# aprs_tracker_v4.net
KiCad netlist of a schematic drawn in EAGLE
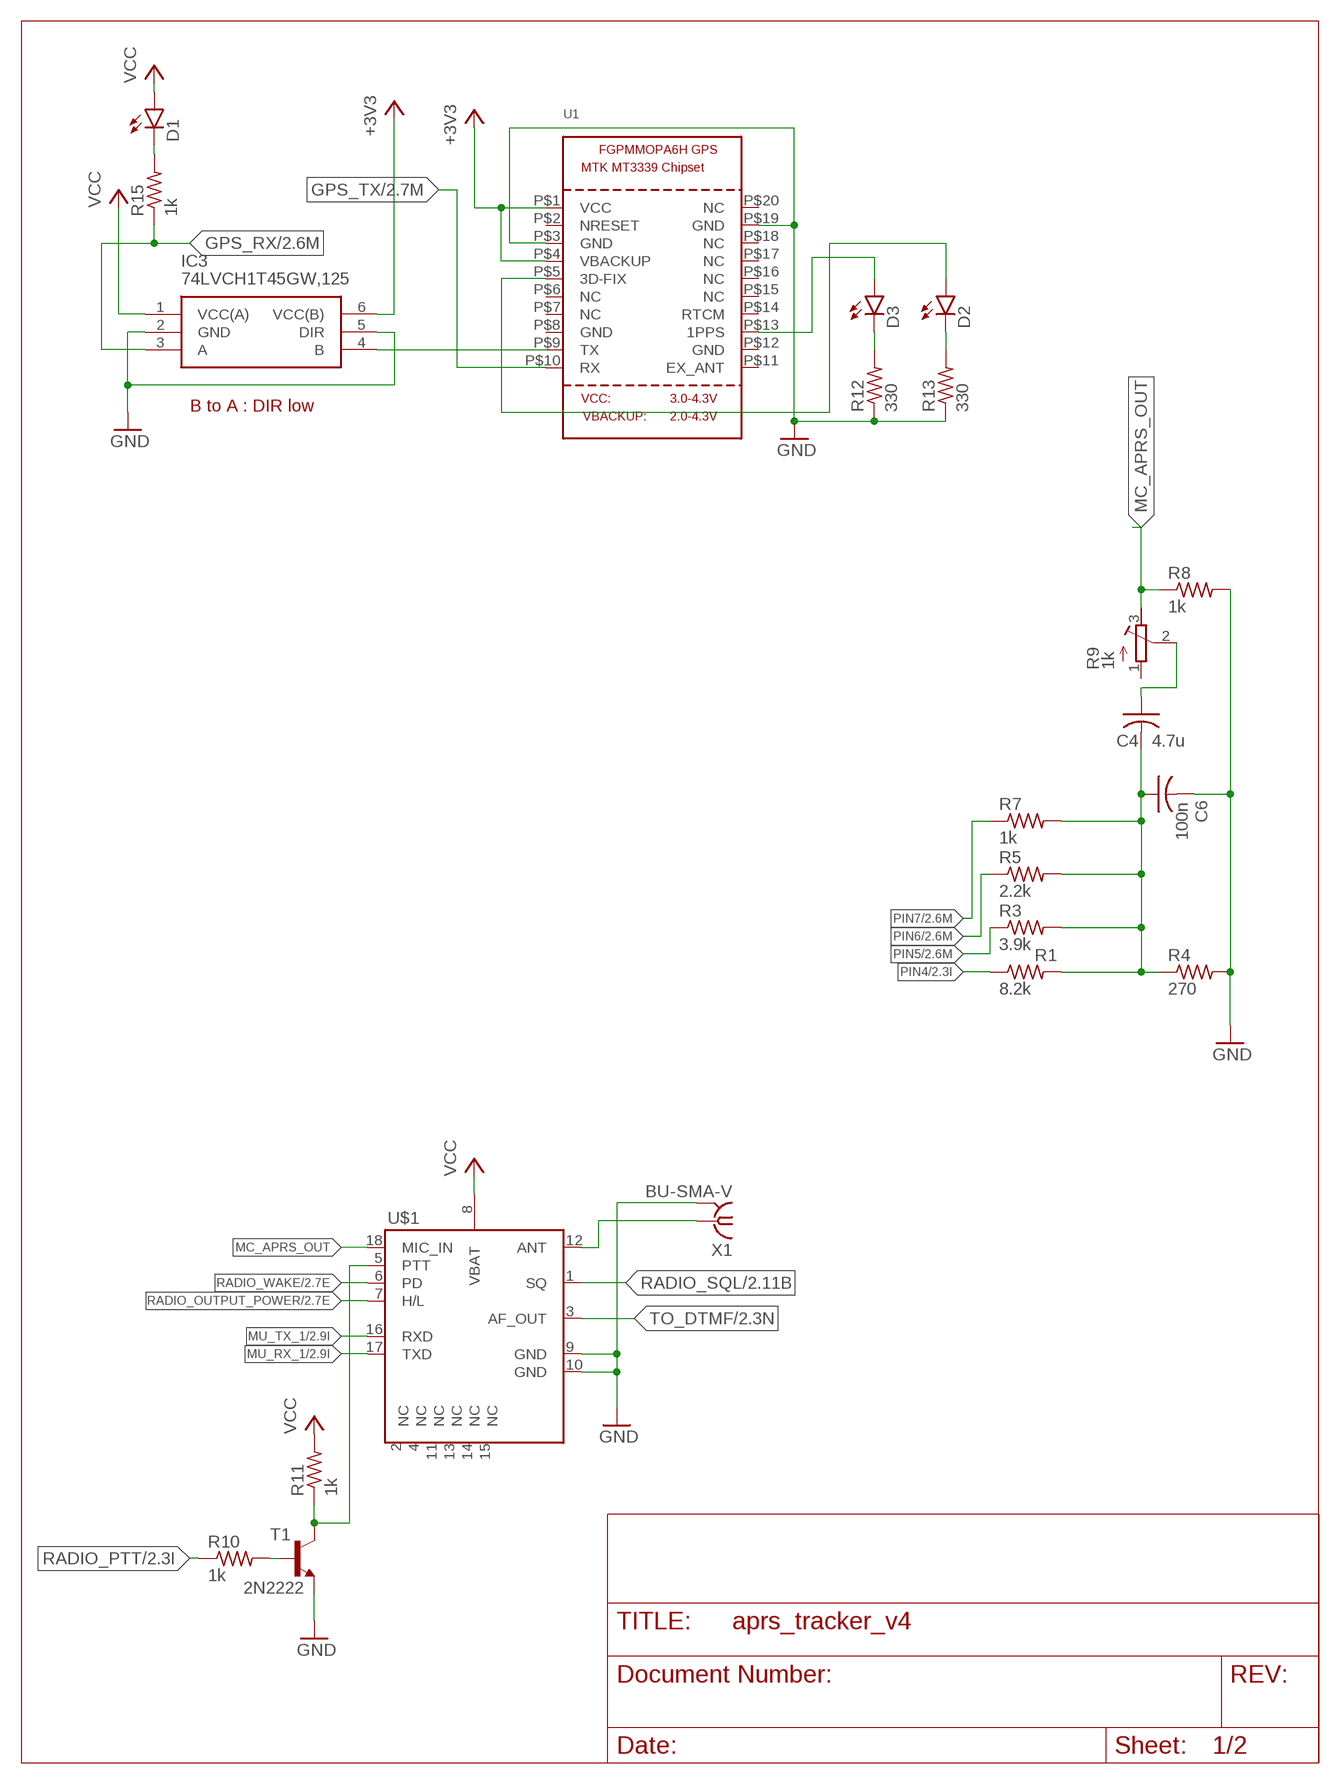
[diagram p0: schematic, sheet 1]
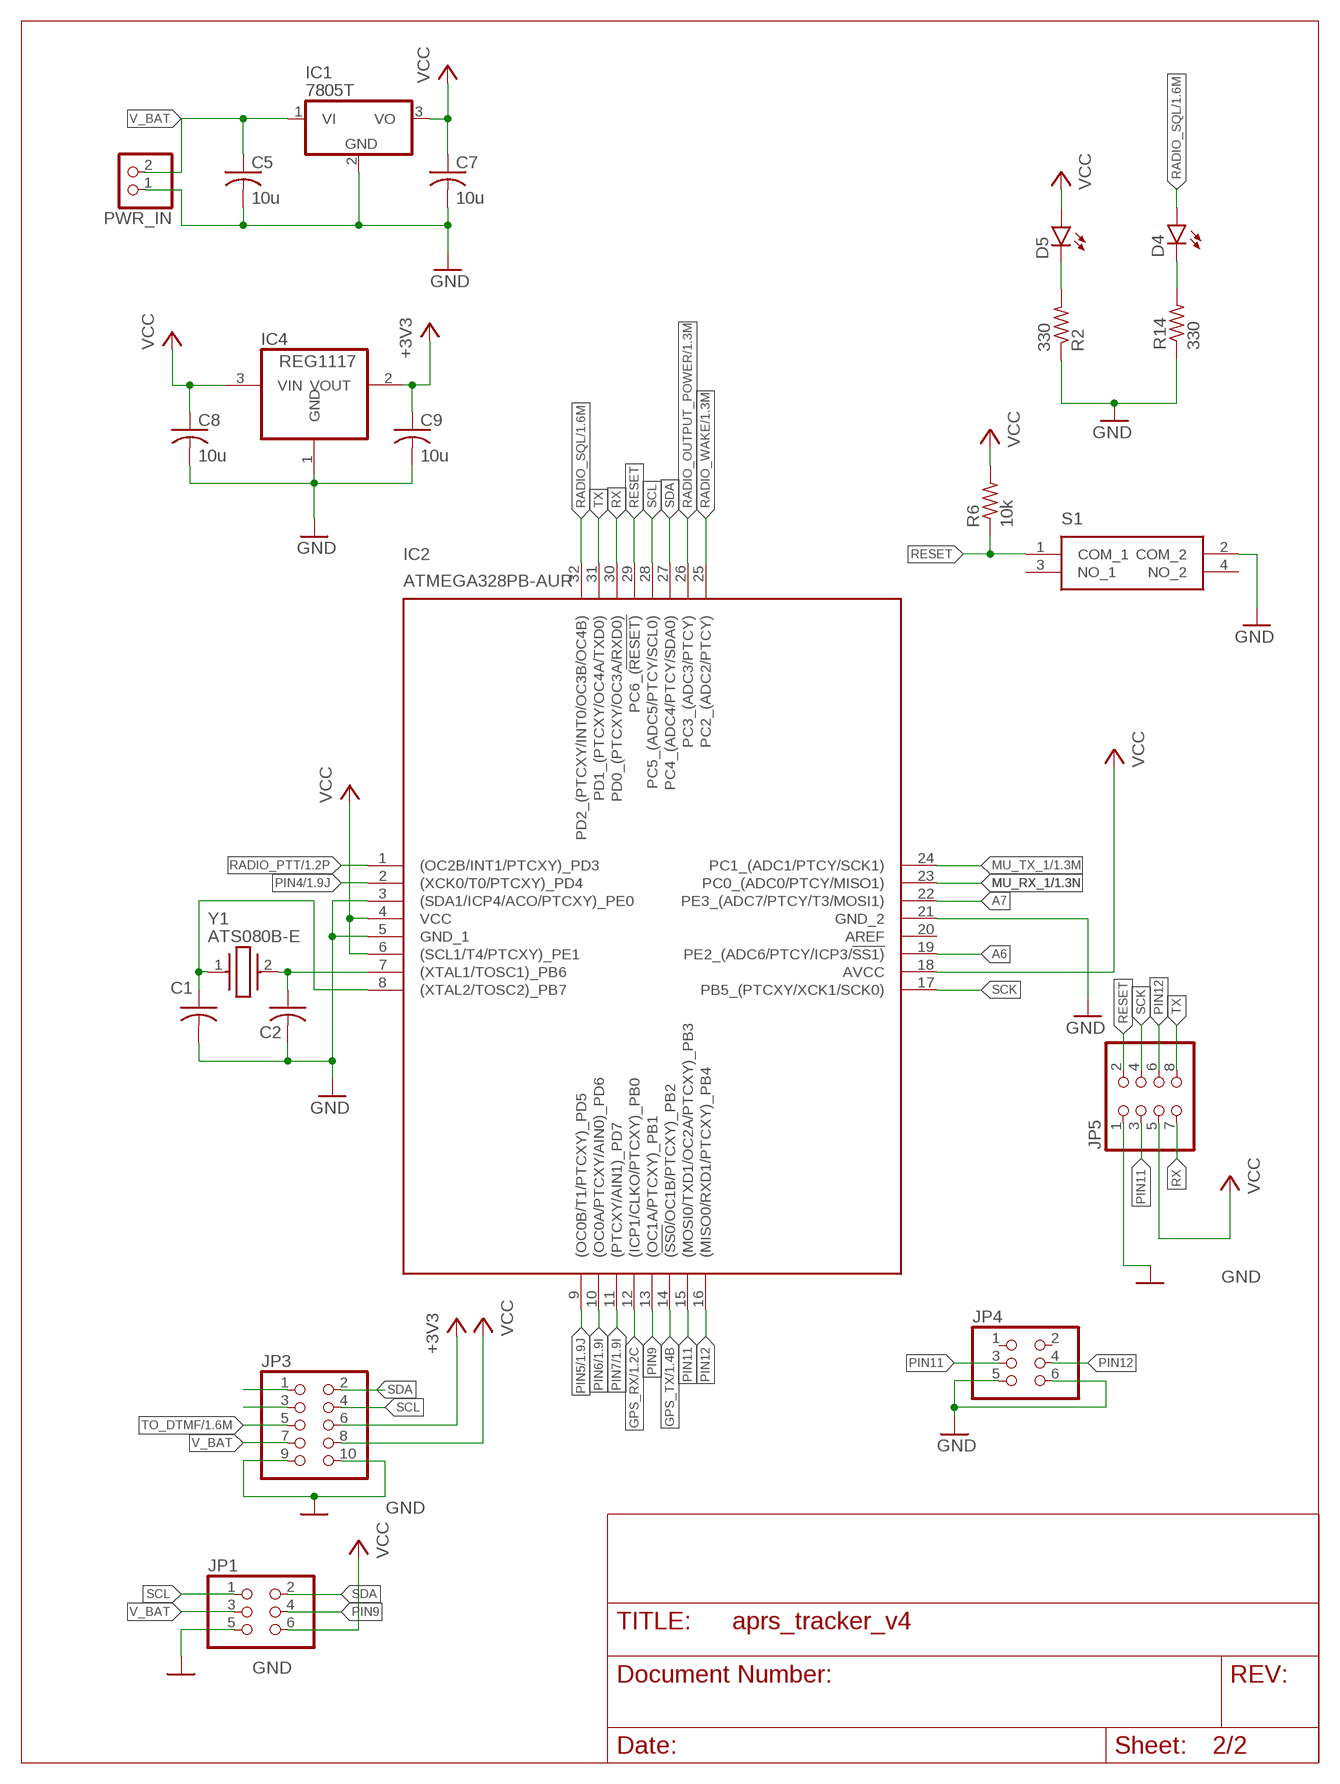
[diagram p1: schematic, sheet 2]

(export (version "E")
  (design (tool "Eeschema 10.0.6"))
  (components
    (comp (ref "C4")
      (value "4.7u")
      (footprint "eagle-import:C0805")
      (libsource (lib "eagle-import") (part "C-USC0805"))
    )
    (comp (ref "C6")
      (value "100n")
      (footprint "eagle-import:C0805")
      (libsource (lib "eagle-import") (part "C-USC0805"))
    )
    (comp (ref "D1")
      (value "LEDCHIP-LED0805")
      (footprint "eagle-import:CHIP-LED0805")
      (libsource (lib "eagle-import") (part "LEDCHIP-LED0805"))
    )
    (comp (ref "D2")
      (value "LEDCHIP-LED0805")
      (footprint "eagle-import:CHIP-LED0805")
      (libsource (lib "eagle-import") (part "LEDCHIP-LED0805"))
    )
    (comp (ref "D3")
      (value "LEDCHIP-LED0805")
      (footprint "eagle-import:CHIP-LED0805")
      (libsource (lib "eagle-import") (part "LEDCHIP-LED0805"))
    )
    (comp (ref "IC3")
      (value "74LVCH1T45GW,125")
      (footprint "eagle-import:74LVCH1T45GW125")
      (fields (field (name "MOUSER_PART_NUMBER") "771-74LVCH1T45GW125"))
      (libsource (lib "eagle-import") (part "74LVCH1T45GW,125"))
    )
    (comp (ref "R1")
      (value "8.2k")
      (footprint "eagle-import:R0805")
      (libsource (lib "eagle-import") (part "R-US_R0805"))
    )
    (comp (ref "R3")
      (value "3.9k")
      (footprint "eagle-import:R0805")
      (libsource (lib "eagle-import") (part "R-US_R0805"))
    )
    (comp (ref "R4")
      (value "270")
      (footprint "eagle-import:R0805")
      (libsource (lib "eagle-import") (part "R-US_R0805"))
    )
    (comp (ref "R5")
      (value "2.2k")
      (footprint "eagle-import:R0805")
      (libsource (lib "eagle-import") (part "R-US_R0805"))
    )
    (comp (ref "R7")
      (value "1k")
      (footprint "eagle-import:R0805")
      (libsource (lib "eagle-import") (part "R-US_R0805"))
    )
    (comp (ref "R8")
      (value "1k")
      (footprint "eagle-import:R0805")
      (libsource (lib "eagle-import") (part "R-US_R0805"))
    )
    (comp (ref "R9")
      (value "1k")
      (footprint "eagle-import:RTRIM3339P")
      (libsource (lib "eagle-import") (part "R-TRIMM3339P"))
    )
    (comp (ref "R10")
      (value "1k")
      (footprint "eagle-import:R0805")
      (libsource (lib "eagle-import") (part "R-US_R0805"))
    )
    (comp (ref "R11")
      (value "1k")
      (footprint "eagle-import:R0805")
      (libsource (lib "eagle-import") (part "R-US_R0805"))
    )
    (comp (ref "R12")
      (value "330")
      (footprint "eagle-import:R0805")
      (libsource (lib "eagle-import") (part "R-US_R0805"))
    )
    (comp (ref "R13")
      (value "330")
      (footprint "eagle-import:R0805")
      (libsource (lib "eagle-import") (part "R-US_R0805"))
    )
    (comp (ref "R15")
      (value "1k")
      (footprint "eagle-import:R0805")
      (libsource (lib "eagle-import") (part "R-US_R0805"))
    )
    (comp (ref "T1")
      (value "2N2222")
      (footprint "eagle-import:TO92-EBC-OVAL")
      (libsource (lib "eagle-import") (part "2N2222"))
    )
    (comp (ref "U$1")
      (value "DRA818A")
      (footprint "eagle-import:DRA818A")
      (libsource (lib "eagle-import") (part "DRA818A"))
    )
    (comp (ref "U1")
      (value "GPS_FGPMMOPA6H")
      (footprint "eagle-import:FGPMMOPA6H")
      (libsource (lib "eagle-import") (part "GPS_FGPMMOPA6H"))
    )
    (comp (ref "X1")
      (value "BU-SMA-V")
      (footprint "eagle-import:BU-SMA-V")
      (libsource (lib "eagle-import") (part "BU-SMA-V"))
    )
    (comp (ref "C1")
      (value "C-USC0805")
      (footprint "eagle-import:C0805")
      (libsource (lib "eagle-import") (part "C-USC0805"))
    )
    (comp (ref "C2")
      (value "C-USC0805")
      (footprint "eagle-import:C0805")
      (libsource (lib "eagle-import") (part "C-USC0805"))
    )
    (comp (ref "C5")
      (value "10u")
      (footprint "eagle-import:C0805")
      (libsource (lib "eagle-import") (part "C-USC0805"))
    )
    (comp (ref "C7")
      (value "10u")
      (footprint "eagle-import:C0805")
      (libsource (lib "eagle-import") (part "C-USC0805"))
    )
    (comp (ref "C8")
      (value "10u")
      (footprint "eagle-import:C0805")
      (libsource (lib "eagle-import") (part "C-USC0805"))
    )
    (comp (ref "C9")
      (value "10u")
      (footprint "eagle-import:C0805")
      (libsource (lib "eagle-import") (part "C-USC0805"))
    )
    (comp (ref "D4")
      (value "LEDCHIP-LED0805")
      (footprint "eagle-import:CHIP-LED0805")
      (libsource (lib "eagle-import") (part "LEDCHIP-LED0805"))
    )
    (comp (ref "D5")
      (value "LEDCHIP-LED0805")
      (footprint "eagle-import:CHIP-LED0805")
      (libsource (lib "eagle-import") (part "LEDCHIP-LED0805"))
    )
    (comp (ref "IC1")
      (value "7805T")
      (footprint "eagle-import:TO220H")
      (libsource (lib "eagle-import") (part "78T05"))
    )
    (comp (ref "IC2")
      (value "ATMEGA328PB-AUR")
      (footprint "eagle-import:QFP80P900X900X120-32N")
      (fields (field (name "MOUSER_PART_NUMBER") "556-ATMEGA328PB-AUR"))
      (libsource (lib "eagle-import") (part "ATMEGA328PB-AUR"))
    )
    (comp (ref "IC4")
      (value "REG1117")
      (footprint "eagle-import:SOT223")
      (libsource (lib "eagle-import") (part "REG1117"))
    )
    (comp (ref "JP1")
      (value "PINHD-2X3/90")
      (footprint "eagle-import:2X03_90")
      (libsource (lib "eagle-import") (part "PINHD-2X3/90"))
    )
    (comp (ref "JP3")
      (value "PINHD-2X5")
      (footprint "eagle-import:2X05")
      (libsource (lib "eagle-import") (part "PINHD-2X5"))
    )
    (comp (ref "JP4")
      (value "PINHD-2X3/90")
      (footprint "eagle-import:2X03_90")
      (libsource (lib "eagle-import") (part "PINHD-2X3/90"))
    )
    (comp (ref "JP5")
      (value "PINHD-2X4")
      (footprint "eagle-import:2X04")
      (libsource (lib "eagle-import") (part "PINHD-2X4"))
    )
    (comp (ref "PWR_IN")
      (value "PINHD-1X2/90")
      (footprint "eagle-import:1X02_90")
      (libsource (lib "eagle-import") (part "PINHD-1X2/90"))
    )
    (comp (ref "R2")
      (value "330")
      (footprint "eagle-import:R0805")
      (libsource (lib "eagle-import") (part "R-US_R0805"))
    )
    (comp (ref "R6")
      (value "10k")
      (footprint "eagle-import:R0805")
      (libsource (lib "eagle-import") (part "R-US_R0805"))
    )
    (comp (ref "R14")
      (value "330")
      (footprint "eagle-import:R0805")
      (libsource (lib "eagle-import") (part "R-US_R0805"))
    )
    (comp (ref "S1")
      (value "PTS526_SK15_SMTR2_LFS")
      (footprint "eagle-import:PTS526SK15SMTR2LFS")
      (fields
        (field (name "MANUFACTURER_PART_NUMBER") "PTS526 SK15 SMTR2 LFS")
        (field (name "MOUSER_PART_NUMBER") "611-PTS526SK15SMR2L")
      )
      (libsource (lib "eagle-import") (part "PTS526_SK15_SMTR2_LFS"))
    )
    (comp (ref "Y1")
      (value "ATS080B-E")
      (footprint "eagle-import:ATS080BE")
      (fields (field (name "MOUSER_PART_NUMBER") "774-ATS080B-E"))
      (libsource (lib "eagle-import") (part "ATS080B-E"))
    )
  )
  (nets
    (net (code "1") (name "+3V3") (class "Default")
      (node (ref "C9") (pin "1") (pinfunction "1_1") (pintype "passive"))
      (node (ref "IC3") (pin "6") (pinfunction "VCC(B)_6") (pintype "bidirectional"))
      (node (ref "IC4") (pin "2") (pinfunction "VOUT_2") (pintype "output"))
      (node (ref "JP3") (pin "6") (pinfunction "6_6") (pintype "passive"))
      (node (ref "U1") (pin "P$1") (pinfunction "VCC_P$1") (pintype "bidirectional"))
      (node (ref "U1") (pin "P$4") (pinfunction "VBACKUP_P$4") (pintype "bidirectional"))
    )
    (net (code "2") (name "A6") (class "Default")
      (node (ref "IC2") (pin "19") (pinfunction "PE2_(ADC6/PTCY/ICP3/~{SS1})_19") (pintype "bidirectional"))
    )
    (net (code "3") (name "A7") (class "Default")
      (node (ref "IC2") (pin "22") (pinfunction "PE3_(ADC7/PTCY/T3/MOSI1)_22") (pintype "bidirectional"))
    )
    (net (code "4") (name "GND") (class "Default")
      (node (ref "C1") (pin "2") (pinfunction "2_2") (pintype "passive"))
      (node (ref "C2") (pin "2") (pinfunction "2_2") (pintype "passive"))
      (node (ref "C5") (pin "2") (pinfunction "2_2") (pintype "passive"))
      (node (ref "C6") (pin "2") (pinfunction "2_2") (pintype "passive"))
      (node (ref "C7") (pin "2") (pinfunction "2_2") (pintype "passive"))
      (node (ref "C8") (pin "2") (pinfunction "2_2") (pintype "passive"))
      (node (ref "C9") (pin "2") (pinfunction "2_2") (pintype "passive"))
      (node (ref "IC1") (pin "2") (pinfunction "GND_2") (pintype "passive"))
      (node (ref "IC2") (pin "21") (pinfunction "GND_2_21") (pintype "bidirectional"))
      (node (ref "IC2") (pin "3") (pinfunction "(SDA1/ICP4/ACO/PTCXY)_PE0_3") (pintype "bidirectional"))
      (node (ref "IC2") (pin "5") (pinfunction "GND_1_5") (pintype "bidirectional"))
      (node (ref "IC3") (pin "2") (pinfunction "GND_2") (pintype "bidirectional"))
      (node (ref "IC3") (pin "5") (pinfunction "DIR_5") (pintype "bidirectional"))
      (node (ref "IC4") (pin "1") (pinfunction "GND_1") (pintype "power_in"))
      (node (ref "JP1") (pin "5") (pinfunction "5_5") (pintype "passive"))
      (node (ref "JP3") (pin "10") (pinfunction "10_10") (pintype "passive"))
      (node (ref "JP3") (pin "9") (pinfunction "9_9") (pintype "passive"))
      (node (ref "JP4") (pin "5") (pinfunction "5_5") (pintype "passive"))
      (node (ref "JP4") (pin "6") (pinfunction "6_6") (pintype "passive"))
      (node (ref "JP5") (pin "1") (pinfunction "1_1") (pintype "passive"))
      (node (ref "PWR_IN") (pin "1") (pinfunction "1_1") (pintype "passive"))
      (node (ref "R12") (pin "1") (pinfunction "1_1") (pintype "passive"))
      (node (ref "R13") (pin "1") (pinfunction "1_1") (pintype "passive"))
      (node (ref "R14") (pin "1") (pinfunction "1_1") (pintype "passive"))
      (node (ref "R2") (pin "1") (pinfunction "1_1") (pintype "passive"))
      (node (ref "R4") (pin "2") (pinfunction "2_2") (pintype "passive"))
      (node (ref "R8") (pin "2") (pinfunction "2_2") (pintype "passive"))
      (node (ref "S1") (pin "2") (pinfunction "COM_2_2") (pintype "bidirectional"))
      (node (ref "T1") (pin "E") (pinfunction "E_E") (pintype "passive"))
      (node (ref "U$1") (pin "10") (pinfunction "GND_10") (pintype "bidirectional"))
      (node (ref "U$1") (pin "9") (pinfunction "GND_9") (pintype "bidirectional"))
      (node (ref "U1") (pin "P$19") (pinfunction "GND_P$19") (pintype "bidirectional"))
      (node (ref "U1") (pin "P$3") (pinfunction "GND_P$3") (pintype "bidirectional"))
      (node (ref "X1") (pin "2") (pinfunction "2_2") (pintype "passive"))
      (node (ref "X1") (pin "3") (pinfunction "2_3") (pintype "passive"))
      (node (ref "X1") (pin "4") (pinfunction "2_4") (pintype "passive"))
      (node (ref "X1") (pin "5") (pinfunction "2_5") (pintype "passive"))
    )
    (net (code "5") (name "GPS_RX") (class "Default")
      (node (ref "IC2") (pin "12") (pinfunction "(ICP1/CLKO/PTCXY)_PB0_12") (pintype "bidirectional"))
      (node (ref "IC3") (pin "3") (pinfunction "A_3") (pintype "bidirectional"))
      (node (ref "R15") (pin "1") (pinfunction "1_1") (pintype "passive"))
    )
    (net (code "6") (name "GPS_TX") (class "Default")
      (node (ref "IC2") (pin "14") (pinfunction "(~{SS0}/OC1B/PTCXY)_PB2_14") (pintype "bidirectional"))
      (node (ref "U1") (pin "P$10") (pinfunction "RX_P$10") (pintype "bidirectional"))
    )
    (net (code "7") (name "MC_APRS_OUT") (class "Default")
      (node (ref "R8") (pin "1") (pinfunction "1_1") (pintype "passive"))
      (node (ref "R9") (pin "3") (pinfunction "E_3") (pintype "passive"))
      (node (ref "U$1") (pin "18") (pinfunction "MIC_IN_18") (pintype "bidirectional"))
    )
    (net (code "8") (name "MU_RX_1") (class "Default")
      (node (ref "IC2") (pin "23") (pinfunction "PC0_(ADC0/PTCY/MISO1)_23") (pintype "bidirectional"))
      (node (ref "U$1") (pin "17") (pinfunction "TXD_17") (pintype "bidirectional"))
    )
    (net (code "9") (name "MU_TX_1") (class "Default")
      (node (ref "IC2") (pin "24") (pinfunction "PC1_(ADC1/PTCY/SCK1)_24") (pintype "bidirectional"))
      (node (ref "U$1") (pin "16") (pinfunction "RXD_16") (pintype "bidirectional"))
    )
    (net (code "10") (name "Net-(C4-Pad2)") (class "Default")
      (node (ref "C4") (pin "2") (pinfunction "2_2") (pintype "passive"))
      (node (ref "C6") (pin "1") (pinfunction "1_1") (pintype "passive"))
      (node (ref "R1") (pin "2") (pinfunction "2_2") (pintype "passive"))
      (node (ref "R3") (pin "2") (pinfunction "2_2") (pintype "passive"))
      (node (ref "R4") (pin "1") (pinfunction "1_1") (pintype "passive"))
      (node (ref "R5") (pin "2") (pinfunction "2_2") (pintype "passive"))
      (node (ref "R7") (pin "2") (pinfunction "2_2") (pintype "passive"))
    )
    (net (code "11") (name "Net-(D1-PadC)") (class "Default")
      (node (ref "D1") (pin "C") (pinfunction "C_C") (pintype "passive"))
      (node (ref "R15") (pin "2") (pinfunction "2_2") (pintype "passive"))
    )
    (net (code "12") (name "Net-(D2-PadC)") (class "Default")
      (node (ref "D2") (pin "C") (pinfunction "C_C") (pintype "passive"))
      (node (ref "R13") (pin "2") (pinfunction "2_2") (pintype "passive"))
    )
    (net (code "13") (name "Net-(D3-PadC)") (class "Default")
      (node (ref "D3") (pin "C") (pinfunction "C_C") (pintype "passive"))
      (node (ref "R12") (pin "2") (pinfunction "2_2") (pintype "passive"))
    )
    (net (code "14") (name "Net-(D4-PadC)") (class "Default")
      (node (ref "D4") (pin "C") (pinfunction "C_C") (pintype "passive"))
      (node (ref "R14") (pin "2") (pinfunction "2_2") (pintype "passive"))
    )
    (net (code "15") (name "Net-(D5-PadC)") (class "Default")
      (node (ref "D5") (pin "C") (pinfunction "C_C") (pintype "passive"))
      (node (ref "R2") (pin "2") (pinfunction "2_2") (pintype "passive"))
    )
    (net (code "16") (name "Net-(IC2-(XTAL1{slash}TOSC1)_PB6)") (class "Default")
      (node (ref "C2") (pin "1") (pinfunction "1_1") (pintype "passive"))
      (node (ref "IC2") (pin "7") (pinfunction "(XTAL1/TOSC1)_PB6_7") (pintype "bidirectional"))
      (node (ref "Y1") (pin "2") (pinfunction "2_2") (pintype "bidirectional"))
    )
    (net (code "17") (name "Net-(IC2-(XTAL2{slash}TOSC2)_PB7)") (class "Default")
      (node (ref "C1") (pin "1") (pinfunction "1_1") (pintype "passive"))
      (node (ref "IC2") (pin "8") (pinfunction "(XTAL2/TOSC2)_PB7_8") (pintype "bidirectional"))
      (node (ref "Y1") (pin "1") (pinfunction "1_1") (pintype "bidirectional"))
    )
    (net (code "18") (name "Net-(IC3-B)") (class "Default")
      (node (ref "IC3") (pin "4") (pinfunction "B_4") (pintype "bidirectional"))
      (node (ref "U1") (pin "P$9") (pinfunction "TX_P$9") (pintype "bidirectional"))
    )
    (net (code "19") (name "Net-(R9-S)") (class "Default")
      (node (ref "C4") (pin "1") (pinfunction "1_1") (pintype "passive"))
      (node (ref "R9") (pin "2") (pinfunction "S_2") (pintype "passive"))
    )
    (net (code "20") (name "Net-(R10-Pad2)") (class "Default")
      (node (ref "R10") (pin "2") (pinfunction "2_2") (pintype "passive"))
      (node (ref "T1") (pin "B") (pinfunction "B_B") (pintype "passive"))
    )
    (net (code "21") (name "Net-(U$1-ANT)") (class "Default")
      (node (ref "U$1") (pin "12") (pinfunction "ANT_12") (pintype "bidirectional"))
      (node (ref "X1") (pin "1") (pinfunction "1_1") (pintype "passive"))
    )
    (net (code "22") (name "Net-(U$1-PTT)") (class "Default")
      (node (ref "R11") (pin "1") (pinfunction "1_1") (pintype "passive"))
      (node (ref "T1") (pin "C") (pinfunction "C_C") (pintype "passive"))
      (node (ref "U$1") (pin "5") (pinfunction "PTT_5") (pintype "bidirectional"))
    )
    (net (code "23") (name "Net-(U1-1PPS)") (class "Default")
      (node (ref "D3") (pin "A") (pinfunction "A_A") (pintype "passive"))
      (node (ref "U1") (pin "P$13") (pinfunction "1PPS_P$13") (pintype "bidirectional"))
    )
    (net (code "24") (name "Net-(U1-3D-FIX)") (class "Default")
      (node (ref "D2") (pin "A") (pinfunction "A_A") (pintype "passive"))
      (node (ref "U1") (pin "P$5") (pinfunction "3D-FIX_P$5") (pintype "bidirectional"))
    )
    (net (code "25") (name "PIN4") (class "Default")
      (node (ref "IC2") (pin "2") (pinfunction "(XCK0/T0/PTCXY)_PD4_2") (pintype "bidirectional"))
      (node (ref "R1") (pin "1") (pinfunction "1_1") (pintype "passive"))
    )
    (net (code "26") (name "PIN5") (class "Default")
      (node (ref "IC2") (pin "9") (pinfunction "(OC0B/T1/PTCXY)_PD5_9") (pintype "bidirectional"))
      (node (ref "R3") (pin "1") (pinfunction "1_1") (pintype "passive"))
    )
    (net (code "27") (name "PIN6") (class "Default")
      (node (ref "IC2") (pin "10") (pinfunction "(OC0A/PTCXY/AIN0)_PD6_10") (pintype "bidirectional"))
      (node (ref "R5") (pin "1") (pinfunction "1_1") (pintype "passive"))
    )
    (net (code "28") (name "PIN7") (class "Default")
      (node (ref "IC2") (pin "11") (pinfunction "(PTCXY/AIN1)_PD7_11") (pintype "bidirectional"))
      (node (ref "R7") (pin "1") (pinfunction "1_1") (pintype "passive"))
    )
    (net (code "29") (name "PIN9") (class "Default")
      (node (ref "IC2") (pin "13") (pinfunction "(OC1A/PTCXY)_PB1_13") (pintype "bidirectional"))
      (node (ref "JP1") (pin "4") (pinfunction "4_4") (pintype "passive"))
    )
    (net (code "30") (name "PIN11") (class "Default")
      (node (ref "IC2") (pin "15") (pinfunction "(MOSI0/TXD1/OC2A/PTCXY)_PB3_15") (pintype "bidirectional"))
      (node (ref "JP4") (pin "3") (pinfunction "3_3") (pintype "passive"))
      (node (ref "JP5") (pin "3") (pinfunction "3_3") (pintype "passive"))
    )
    (net (code "31") (name "PIN12") (class "Default")
      (node (ref "IC2") (pin "16") (pinfunction "(MISO0/RXD1/PTCXY)_PB4_16") (pintype "bidirectional"))
      (node (ref "JP4") (pin "4") (pinfunction "4_4") (pintype "passive"))
      (node (ref "JP5") (pin "6") (pinfunction "6_6") (pintype "passive"))
    )
    (net (code "32") (name "RADIO_OUTPUT_POWER") (class "Default")
      (node (ref "IC2") (pin "26") (pinfunction "PC3_(ADC3/PTCY)_26") (pintype "bidirectional"))
      (node (ref "U$1") (pin "7") (pinfunction "H/L_7") (pintype "bidirectional"))
    )
    (net (code "33") (name "RADIO_PTT") (class "Default")
      (node (ref "IC2") (pin "1") (pinfunction "(OC2B/INT1/PTCXY)_PD3_1") (pintype "bidirectional"))
      (node (ref "R10") (pin "1") (pinfunction "1_1") (pintype "passive"))
    )
    (net (code "34") (name "RADIO_SQL") (class "Default")
      (node (ref "D4") (pin "A") (pinfunction "A_A") (pintype "passive"))
      (node (ref "IC2") (pin "32") (pinfunction "PD2_(PTCXY/INT0/OC3B/OC4B)_32") (pintype "bidirectional"))
      (node (ref "U$1") (pin "1") (pinfunction "SQ_1") (pintype "bidirectional"))
    )
    (net (code "35") (name "RADIO_WAKE") (class "Default")
      (node (ref "IC2") (pin "25") (pinfunction "PC2_(ADC2/PTCY)_25") (pintype "bidirectional"))
      (node (ref "U$1") (pin "6") (pinfunction "PD_6") (pintype "bidirectional"))
    )
    (net (code "36") (name "RESET") (class "Default")
      (node (ref "IC2") (pin "29") (pinfunction "PC6_(~{RESET})_29") (pintype "bidirectional"))
      (node (ref "JP5") (pin "2") (pinfunction "2_2") (pintype "passive"))
      (node (ref "R6") (pin "1") (pinfunction "1_1") (pintype "passive"))
      (node (ref "S1") (pin "1") (pinfunction "COM_1_1") (pintype "bidirectional"))
    )
    (net (code "37") (name "RX") (class "Default")
      (node (ref "IC2") (pin "30") (pinfunction "PD0_(PTCXY/OC3A/RXD0)_30") (pintype "bidirectional"))
      (node (ref "JP5") (pin "7") (pinfunction "7_7") (pintype "passive"))
    )
    (net (code "38") (name "SCK") (class "Default")
      (node (ref "IC2") (pin "17") (pinfunction "PB5_(PTCXY/XCK1/SCK0)_17") (pintype "bidirectional"))
      (node (ref "JP5") (pin "4") (pinfunction "4_4") (pintype "passive"))
    )
    (net (code "39") (name "SCL") (class "Default")
      (node (ref "IC2") (pin "28") (pinfunction "PC5_(ADC5/PTCY/SCL0)_28") (pintype "bidirectional"))
      (node (ref "JP1") (pin "1") (pinfunction "1_1") (pintype "passive"))
      (node (ref "JP3") (pin "4") (pinfunction "4_4") (pintype "passive"))
    )
    (net (code "40") (name "SDA") (class "Default")
      (node (ref "IC2") (pin "27") (pinfunction "PC4_(ADC4/PTCY/SDA0)_27") (pintype "bidirectional"))
      (node (ref "JP1") (pin "2") (pinfunction "2_2") (pintype "passive"))
      (node (ref "JP3") (pin "2") (pinfunction "2_2") (pintype "passive"))
    )
    (net (code "41") (name "TO_DTMF") (class "Default")
      (node (ref "JP3") (pin "5") (pinfunction "5_5") (pintype "passive"))
      (node (ref "U$1") (pin "3") (pinfunction "AF_OUT_3") (pintype "bidirectional"))
    )
    (net (code "42") (name "TX") (class "Default")
      (node (ref "IC2") (pin "31") (pinfunction "PD1_(PTCXY/OC4A/TXD0)_31") (pintype "bidirectional"))
      (node (ref "JP5") (pin "8") (pinfunction "8_8") (pintype "passive"))
    )
    (net (code "43") (name "VCC") (class "Default")
      (node (ref "C7") (pin "1") (pinfunction "1_1") (pintype "passive"))
      (node (ref "C8") (pin "1") (pinfunction "1_1") (pintype "passive"))
      (node (ref "D1") (pin "A") (pinfunction "A_A") (pintype "passive"))
      (node (ref "D5") (pin "A") (pinfunction "A_A") (pintype "passive"))
      (node (ref "IC1") (pin "3") (pinfunction "VO_3") (pintype "passive"))
      (node (ref "IC2") (pin "18") (pinfunction "AVCC_18") (pintype "bidirectional"))
      (node (ref "IC2") (pin "4") (pinfunction "VCC_4") (pintype "bidirectional"))
      (node (ref "IC2") (pin "6") (pinfunction "(SCL1/T4/PTCXY)_PE1_6") (pintype "bidirectional"))
      (node (ref "IC3") (pin "1") (pinfunction "VCC(A)_1") (pintype "bidirectional"))
      (node (ref "IC4") (pin "3") (pinfunction "VIN_3") (pintype "input"))
      (node (ref "JP1") (pin "6") (pinfunction "6_6") (pintype "passive"))
      (node (ref "JP3") (pin "8") (pinfunction "8_8") (pintype "passive"))
      (node (ref "JP5") (pin "5") (pinfunction "5_5") (pintype "passive"))
      (node (ref "R11") (pin "2") (pinfunction "2_2") (pintype "passive"))
      (node (ref "R6") (pin "2") (pinfunction "2_2") (pintype "passive"))
      (node (ref "U$1") (pin "8") (pinfunction "VBAT_8") (pintype "bidirectional"))
    )
    (net (code "44") (name "V_BAT") (class "Default")
      (node (ref "C5") (pin "1") (pinfunction "1_1") (pintype "passive"))
      (node (ref "IC1") (pin "1") (pinfunction "VI_1") (pintype "input"))
      (node (ref "JP1") (pin "3") (pinfunction "3_3") (pintype "passive"))
      (node (ref "JP3") (pin "7") (pinfunction "7_7") (pintype "passive"))
      (node (ref "PWR_IN") (pin "2") (pinfunction "2_2") (pintype "passive"))
    )
    (net (code "45") (name "unconnected-(IC2-AREF-Pad20)") (class "Default")
      (node (ref "IC2") (pin "20") (pinfunction "AREF_20") (pintype "bidirectional"))
    )
    (net (code "46") (name "unconnected-(JP3-Pad1)") (class "Default")
      (node (ref "JP3") (pin "1") (pinfunction "1_1") (pintype "passive"))
    )
    (net (code "47") (name "unconnected-(JP3-Pad3)") (class "Default")
      (node (ref "JP3") (pin "3") (pinfunction "3_3") (pintype "passive"))
    )
    (net (code "48") (name "unconnected-(JP4-Pad1)") (class "Default")
      (node (ref "JP4") (pin "1") (pinfunction "1_1") (pintype "passive"))
    )
    (net (code "49") (name "unconnected-(JP4-Pad2)") (class "Default")
      (node (ref "JP4") (pin "2") (pinfunction "2_2") (pintype "passive"))
    )
    (net (code "50") (name "unconnected-(R9-A-Pad1)") (class "Default")
      (node (ref "R9") (pin "1") (pinfunction "A_1") (pintype "passive"))
    )
    (net (code "51") (name "unconnected-(S1-NO_1-Pad3)") (class "Default")
      (node (ref "S1") (pin "3") (pinfunction "NO_1_3") (pintype "bidirectional"))
    )
    (net (code "52") (name "unconnected-(S1-NO_2-Pad4)") (class "Default")
      (node (ref "S1") (pin "4") (pinfunction "NO_2_4") (pintype "bidirectional"))
    )
    (net (code "53") (name "unconnected-(U$1-NC-Pad2)") (class "Default")
      (node (ref "U$1") (pin "2") (pinfunction "NC_2") (pintype "bidirectional"))
    )
    (net (code "54") (name "unconnected-(U$1-NC-Pad4)") (class "Default")
      (node (ref "U$1") (pin "4") (pinfunction "NC_4") (pintype "bidirectional"))
    )
    (net (code "55") (name "unconnected-(U$1-NC-Pad11)") (class "Default")
      (node (ref "U$1") (pin "11") (pinfunction "NC_11") (pintype "bidirectional"))
    )
    (net (code "56") (name "unconnected-(U$1-NC-Pad13)") (class "Default")
      (node (ref "U$1") (pin "13") (pinfunction "NC_13") (pintype "bidirectional"))
    )
    (net (code "57") (name "unconnected-(U$1-NC-Pad14)") (class "Default")
      (node (ref "U$1") (pin "14") (pinfunction "NC_14") (pintype "bidirectional"))
    )
    (net (code "58") (name "unconnected-(U$1-NC-Pad15)") (class "Default")
      (node (ref "U$1") (pin "15") (pinfunction "NC_15") (pintype "bidirectional"))
    )
    (net (code "59") (name "unconnected-(U1-EX_ANT-PadP$11)") (class "Default")
      (node (ref "U1") (pin "P$11") (pinfunction "EX_ANT_P$11") (pintype "bidirectional"))
    )
    (net (code "60") (name "unconnected-(U1-GND-PadP$8)") (class "Default")
      (node (ref "U1") (pin "P$8") (pinfunction "GND_P$8") (pintype "bidirectional"))
    )
    (net (code "61") (name "unconnected-(U1-GND-PadP$12)") (class "Default")
      (node (ref "U1") (pin "P$12") (pinfunction "GND_P$12") (pintype "bidirectional"))
    )
    (net (code "62") (name "unconnected-(U1-NC-PadP$6)") (class "Default")
      (node (ref "U1") (pin "P$6") (pinfunction "NC_P$6") (pintype "bidirectional"))
    )
    (net (code "63") (name "unconnected-(U1-NC-PadP$7)") (class "Default")
      (node (ref "U1") (pin "P$7") (pinfunction "NC_P$7") (pintype "bidirectional"))
    )
    (net (code "64") (name "unconnected-(U1-NC-PadP$15)") (class "Default")
      (node (ref "U1") (pin "P$15") (pinfunction "NC_P$15") (pintype "bidirectional"))
    )
    (net (code "65") (name "unconnected-(U1-NC-PadP$16)") (class "Default")
      (node (ref "U1") (pin "P$16") (pinfunction "NC_P$16") (pintype "bidirectional"))
    )
    (net (code "66") (name "unconnected-(U1-NC-PadP$17)") (class "Default")
      (node (ref "U1") (pin "P$17") (pinfunction "NC_P$17") (pintype "bidirectional"))
    )
    (net (code "67") (name "unconnected-(U1-NC-PadP$18)") (class "Default")
      (node (ref "U1") (pin "P$18") (pinfunction "NC_P$18") (pintype "bidirectional"))
    )
    (net (code "68") (name "unconnected-(U1-NC-PadP$20)") (class "Default")
      (node (ref "U1") (pin "P$20") (pinfunction "NC_P$20") (pintype "bidirectional"))
    )
    (net (code "69") (name "unconnected-(U1-NRESET-PadP$2)") (class "Default")
      (node (ref "U1") (pin "P$2") (pinfunction "NRESET_P$2") (pintype "bidirectional"))
    )
    (net (code "70") (name "unconnected-(U1-RTCM-PadP$14)") (class "Default")
      (node (ref "U1") (pin "P$14") (pinfunction "RTCM_P$14") (pintype "bidirectional"))
    )
  )
)
